# Breakout3v2.net
KiCad netlist of a schematic drawn in EAGLE
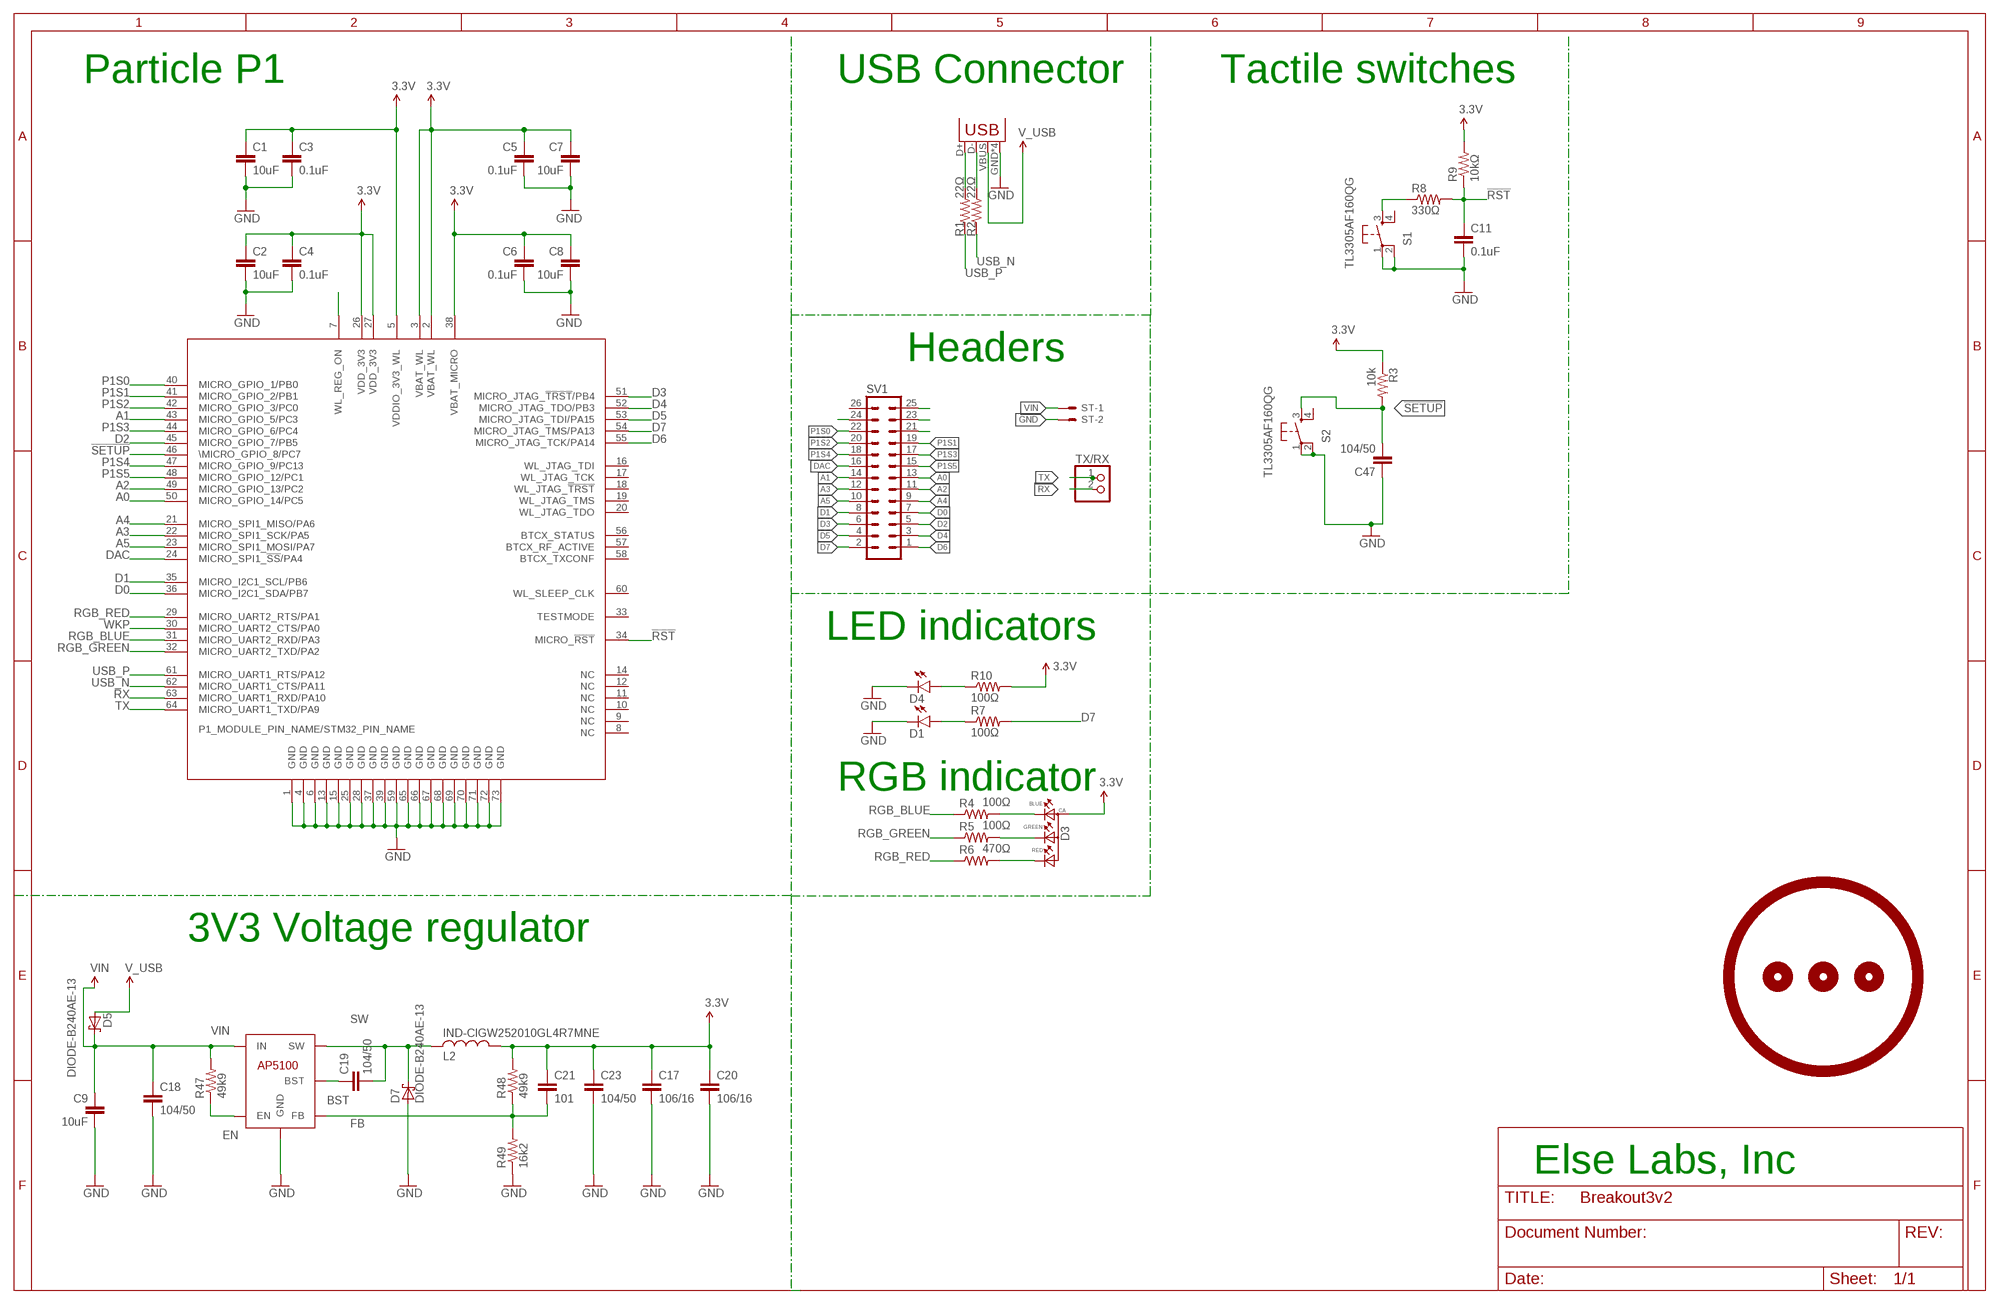
[diagram p0: schematic, sheet 1]

(export (version "E")
  (design (tool "Eeschema 10.0.6"))
  (components
    (comp (ref "C1")
      (value "10uF")
      (footprint "eagle-import:0805")
      (libsource (lib "eagle-import") (part "CAP0805"))
    )
    (comp (ref "C2")
      (value "10uF")
      (footprint "eagle-import:0805")
      (libsource (lib "eagle-import") (part "CAP0805"))
    )
    (comp (ref "C3")
      (value "0.1uF")
      (footprint "eagle-import:0805")
      (libsource (lib "eagle-import") (part "CAP0805"))
    )
    (comp (ref "C4")
      (value "0.1uF")
      (footprint "eagle-import:0805")
      (libsource (lib "eagle-import") (part "CAP0805"))
    )
    (comp (ref "C5")
      (value "0.1uF")
      (footprint "eagle-import:0805")
      (libsource (lib "eagle-import") (part "CAP0805"))
    )
    (comp (ref "C6")
      (value "0.1uF")
      (footprint "eagle-import:0805")
      (libsource (lib "eagle-import") (part "CAP0805"))
    )
    (comp (ref "C7")
      (value "10uF")
      (footprint "eagle-import:0805")
      (libsource (lib "eagle-import") (part "CAP0805"))
    )
    (comp (ref "C8")
      (value "10uF")
      (footprint "eagle-import:0805")
      (libsource (lib "eagle-import") (part "CAP0805"))
    )
    (comp (ref "C9")
      (value "10uF")
      (footprint "eagle-import:0805")
      (libsource (lib "eagle-import") (part "CAP0805"))
    )
    (comp (ref "C11")
      (value "0.1uF")
      (footprint "eagle-import:0805")
      (libsource (lib "eagle-import") (part "CAP0805"))
    )
    (comp (ref "C17")
      (value "106/16")
      (footprint "eagle-import:C0805")
      (libsource (lib "eagle-import") (part "C-EUC0805"))
    )
    (comp (ref "C18")
      (value "104/50")
      (footprint "eagle-import:C0603")
      (libsource (lib "eagle-import") (part "C-EUC0603"))
    )
    (comp (ref "C19")
      (value "104/50")
      (footprint "eagle-import:C0603")
      (libsource (lib "eagle-import") (part "C-EUC0603"))
    )
    (comp (ref "C20")
      (value "106/16")
      (footprint "eagle-import:C0805")
      (libsource (lib "eagle-import") (part "C-EUC0805"))
    )
    (comp (ref "C21")
      (value "101")
      (footprint "eagle-import:C0603")
      (libsource (lib "eagle-import") (part "C-EUC0603"))
    )
    (comp (ref "C23")
      (value "104/50")
      (footprint "eagle-import:C0603")
      (libsource (lib "eagle-import") (part "C-EUC0603"))
    )
    (comp (ref "C47")
      (value "104/50")
      (footprint "eagle-import:C0603")
      (libsource (lib "eagle-import") (part "C-EUC0603"))
    )
    (comp (ref "D1")
      (value "LED0603")
      (footprint "eagle-import:LED-0603")
      (libsource (lib "eagle-import") (part "LED0603"))
    )
    (comp (ref "D3")
      (value "CLVBA-FKAPLCC")
      (footprint "eagle-import:4-PLCC")
      (libsource (lib "eagle-import") (part "CLVBA-FKAPLCC"))
    )
    (comp (ref "D4")
      (value "LED0603")
      (footprint "eagle-import:LED-0603")
      (libsource (lib "eagle-import") (part "LED0603"))
    )
    (comp (ref "D5")
      (value "DIODE-B240AE-13")
      (footprint "eagle-import:DO-214AC")
      (libsource (lib "eagle-import") (part "DIODE-B240AE-13"))
    )
    (comp (ref "D7")
      (value "DIODE-B240AE-13")
      (footprint "eagle-import:DO-214AC")
      (libsource (lib "eagle-import") (part "DIODE-B240AE-13"))
    )
    (comp (ref "IC5")
      (value "SMSP-BUCK-AP5100")
      (footprint "eagle-import:SOT23-6")
      (libsource (lib "eagle-import") (part "SMSP-BUCK-AP5100"))
    )
    (comp (ref "JP1")
      (value "USBUSB-MICROB-SLOT-HOLE")
      (footprint "eagle-import:USB-MICROB-SLOT-HOLE")
      (libsource (lib "eagle-import") (part "USBUSB-MICROB-SLOT-HOLE"))
    )
    (comp (ref "L2")
      (value "IND-CIGW252010GL4R7MNE")
      (footprint "eagle-import:L2520")
      (libsource (lib "eagle-import") (part "IND-CIGW252010GL4R7MNE"))
    )
    (comp (ref "R1")
      (value "22Ω")
      (footprint "eagle-import:0805")
      (libsource (lib "eagle-import") (part "RESISTOR0805-RES"))
    )
    (comp (ref "R2")
      (value "22Ω")
      (footprint "eagle-import:0805")
      (libsource (lib "eagle-import") (part "RESISTOR0805-RES"))
    )
    (comp (ref "R3")
      (value "10k")
      (footprint "eagle-import:R0603")
      (libsource (lib "eagle-import") (part "R-US_R0603"))
    )
    (comp (ref "R4")
      (value "100Ω")
      (footprint "eagle-import:0805")
      (libsource (lib "eagle-import") (part "RESISTOR0805-RES"))
    )
    (comp (ref "R5")
      (value "100Ω")
      (footprint "eagle-import:0805")
      (libsource (lib "eagle-import") (part "RESISTOR0805-RES"))
    )
    (comp (ref "R6")
      (value "470Ω")
      (footprint "eagle-import:0805")
      (libsource (lib "eagle-import") (part "RESISTOR0805-RES"))
    )
    (comp (ref "R7")
      (value "100Ω")
      (footprint "eagle-import:0805")
      (libsource (lib "eagle-import") (part "RESISTOR0805-RES"))
    )
    (comp (ref "R8")
      (value "330Ω")
      (footprint "eagle-import:0805")
      (libsource (lib "eagle-import") (part "RESISTOR0805-RES"))
    )
    (comp (ref "R9")
      (value "10kΩ")
      (footprint "eagle-import:0805")
      (libsource (lib "eagle-import") (part "RESISTOR0805-RES"))
    )
    (comp (ref "R10")
      (value "100Ω")
      (footprint "eagle-import:0805")
      (libsource (lib "eagle-import") (part "RESISTOR0805-RES"))
    )
    (comp (ref "R47")
      (value "49k9")
      (footprint "eagle-import:R0603")
      (libsource (lib "eagle-import") (part "R-US_R0603"))
    )
    (comp (ref "R48")
      (value "49k9")
      (footprint "eagle-import:R0603")
      (libsource (lib "eagle-import") (part "R-US_R0603"))
    )
    (comp (ref "R49")
      (value "16k2")
      (footprint "eagle-import:R0603")
      (libsource (lib "eagle-import") (part "R-US_R0603"))
    )
    (comp (ref "S1")
      (value "TL3305AF160QG")
      (footprint "eagle-import:TACTILE_SWITCH_SMD_4.5X4.5MM")
      (libsource (lib "eagle-import") (part "SWITCH-MOMENTARY-4.5MX4.5M"))
    )
    (comp (ref "S2")
      (value "TL3305AF160QG")
      (footprint "eagle-import:TACTILE_SWITCH_SMD_4.5X4.5MM")
      (libsource (lib "eagle-import") (part "SWITCH-MOMENTARY-4.5MX4.5M"))
    )
    (comp (ref "ST")
      (value "22-27-2021-02")
      (footprint "eagle-import:6410-02")
      (fields (field (name "MF") "MOLEX"))
      (libsource (lib "eagle-import") (part "22-?-0227-2021"))
    )
    (comp (ref "SV1")
      (value "MA13-2")
      (footprint "eagle-import:MA13-2")
      (libsource (lib "eagle-import") (part "MA13-2"))
    )
    (comp (ref "TX/RX")
      (value "PINHD-1X2")
      (footprint "eagle-import:1X02")
      (libsource (lib "eagle-import") (part "PINHD-1X2"))
    )
    (comp (ref "U$1")
      (value "LOGO")
      (footprint "eagle-import:LOGO")
      (libsource (lib "eagle-import") (part "LOGO"))
    )
    (comp (ref "UC1")
      (value "P1")
      (footprint "eagle-import:WM-N-BM-14")
      (libsource (lib "eagle-import") (part "P1"))
    )
  )
  (nets
    (net (code "1") (name "/BST") (class "Default")
      (node (ref "C19") (pin "1") (pinfunction "1_1") (pintype "passive"))
      (node (ref "IC5") (pin "1") (pinfunction "BST_1") (pintype "bidirectional"))
    )
    (net (code "2") (name "/EN") (class "Default")
      (node (ref "IC5") (pin "4") (pinfunction "EN_4") (pintype "bidirectional"))
      (node (ref "R47") (pin "1") (pinfunction "1_1") (pintype "passive"))
    )
    (net (code "3") (name "/FB") (class "Default")
      (node (ref "C21") (pin "2") (pinfunction "2_2") (pintype "passive"))
      (node (ref "IC5") (pin "3") (pinfunction "FB_3") (pintype "bidirectional"))
      (node (ref "R48") (pin "1") (pinfunction "1_1") (pintype "passive"))
      (node (ref "R49") (pin "2") (pinfunction "2_2") (pintype "passive"))
    )
    (net (code "4") (name "/RGB_BLUE") (class "Default")
      (node (ref "R4") (pin "1") (pinfunction "1_1") (pintype "passive"))
      (node (ref "UC1") (pin "31") (pinfunction "MICRO_UART2_RXD/PA3_31") (pintype "bidirectional"))
    )
    (net (code "5") (name "/RGB_GREEN") (class "Default")
      (node (ref "R5") (pin "1") (pinfunction "1_1") (pintype "passive"))
      (node (ref "UC1") (pin "32") (pinfunction "MICRO_UART2_TXD/PA2_32") (pintype "bidirectional"))
    )
    (net (code "6") (name "/RGB_RED") (class "Default")
      (node (ref "R6") (pin "1") (pinfunction "1_1") (pintype "passive"))
      (node (ref "UC1") (pin "29") (pinfunction "MICRO_UART2_RTS/PA1_29") (pintype "bidirectional"))
    )
    (net (code "7") (name "/SW") (class "Default")
      (node (ref "C19") (pin "2") (pinfunction "2_2") (pintype "passive"))
      (node (ref "D7") (pin "C") (pinfunction "C_C") (pintype "passive"))
      (node (ref "IC5") (pin "6") (pinfunction "SW_6") (pintype "bidirectional"))
      (node (ref "L2") (pin "P$2") (pinfunction "2_P$2") (pintype "passive"))
    )
    (net (code "8") (name "/USB_N") (class "Default")
      (node (ref "R2") (pin "1") (pinfunction "1_1") (pintype "passive"))
      (node (ref "UC1") (pin "62") (pinfunction "MICRO_UART1_CTS/PA11_62") (pintype "bidirectional"))
    )
    (net (code "9") (name "/USB_P") (class "Default")
      (node (ref "R1") (pin "1") (pinfunction "1_1") (pintype "passive"))
      (node (ref "UC1") (pin "61") (pinfunction "MICRO_UART1_RTS/PA12_61") (pintype "bidirectional"))
    )
    (net (code "10") (name "/WKP") (class "Default")
      (node (ref "UC1") (pin "30") (pinfunction "MICRO_UART2_CTS/PA0_30") (pintype "bidirectional"))
    )
    (net (code "11") (name "/~{RST}") (class "Default")
      (node (ref "C11") (pin "1") (pinfunction "1_1") (pintype "passive"))
      (node (ref "R8") (pin "2") (pinfunction "2_2") (pintype "passive"))
      (node (ref "R9") (pin "1") (pinfunction "1_1") (pintype "passive"))
      (node (ref "UC1") (pin "34") (pinfunction "MICRO_~{RST}_34") (pintype "bidirectional"))
    )
    (net (code "12") (name "/~{SETUP}") (class "Default")
      (node (ref "C47") (pin "2") (pinfunction "2_2") (pintype "passive"))
      (node (ref "R3") (pin "2") (pinfunction "2_2") (pintype "passive"))
      (node (ref "S2") (pin "3") (pinfunction "3_3") (pintype "passive"))
      (node (ref "UC1") (pin "46") (pinfunction "\\MICRO_GPIO_8/PC7_46") (pintype "bidirectional"))
    )
    (net (code "13") (name "3.3V") (class "Default")
      (node (ref "C1") (pin "1") (pinfunction "1_1") (pintype "passive"))
      (node (ref "C17") (pin "1") (pinfunction "1_1") (pintype "passive"))
      (node (ref "C2") (pin "1") (pinfunction "1_1") (pintype "passive"))
      (node (ref "C20") (pin "1") (pinfunction "1_1") (pintype "passive"))
      (node (ref "C21") (pin "1") (pinfunction "1_1") (pintype "passive"))
      (node (ref "C23") (pin "1") (pinfunction "1_1") (pintype "passive"))
      (node (ref "C3") (pin "1") (pinfunction "1_1") (pintype "passive"))
      (node (ref "C4") (pin "1") (pinfunction "1_1") (pintype "passive"))
      (node (ref "C5") (pin "1") (pinfunction "1_1") (pintype "passive"))
      (node (ref "C6") (pin "1") (pinfunction "1_1") (pintype "passive"))
      (node (ref "C7") (pin "1") (pinfunction "1_1") (pintype "passive"))
      (node (ref "C8") (pin "1") (pinfunction "1_1") (pintype "passive"))
      (node (ref "D3") (pin "2") (pinfunction "ANODE_2") (pintype "passive"))
      (node (ref "L2") (pin "P$1") (pinfunction "1_P$1") (pintype "passive"))
      (node (ref "R10") (pin "2") (pinfunction "2_2") (pintype "passive"))
      (node (ref "R3") (pin "1") (pinfunction "1_1") (pintype "passive"))
      (node (ref "R48") (pin "2") (pinfunction "2_2") (pintype "passive"))
      (node (ref "R9") (pin "2") (pinfunction "2_2") (pintype "passive"))
      (node (ref "UC1") (pin "2") (pinfunction "VBAT_WL_2") (pintype "bidirectional"))
      (node (ref "UC1") (pin "26") (pinfunction "VDD_3V3_26") (pintype "bidirectional"))
      (node (ref "UC1") (pin "27") (pinfunction "VDD_3V3_27") (pintype "bidirectional"))
      (node (ref "UC1") (pin "3") (pinfunction "VBAT_WL_3") (pintype "bidirectional"))
      (node (ref "UC1") (pin "38") (pinfunction "VBAT_MICRO_38") (pintype "bidirectional"))
      (node (ref "UC1") (pin "5") (pinfunction "VDDIO_3V3_WL_5") (pintype "bidirectional"))
    )
    (net (code "14") (name "A0") (class "Default")
      (node (ref "SV1") (pin "13") (pinfunction "13_13") (pintype "passive"))
      (node (ref "UC1") (pin "50") (pinfunction "MICRO_GPIO_14/PC5_50") (pintype "bidirectional"))
    )
    (net (code "15") (name "A1") (class "Default")
      (node (ref "SV1") (pin "14") (pinfunction "14_14") (pintype "passive"))
      (node (ref "UC1") (pin "43") (pinfunction "MICRO_GPIO_5/PC3_43") (pintype "bidirectional"))
    )
    (net (code "16") (name "A2") (class "Default")
      (node (ref "SV1") (pin "11") (pinfunction "11_11") (pintype "passive"))
      (node (ref "UC1") (pin "49") (pinfunction "MICRO_GPIO_13/PC2_49") (pintype "bidirectional"))
    )
    (net (code "17") (name "A3") (class "Default")
      (node (ref "SV1") (pin "12") (pinfunction "12_12") (pintype "passive"))
      (node (ref "UC1") (pin "22") (pinfunction "MICRO_SPI1_SCK/PA5_22") (pintype "bidirectional"))
    )
    (net (code "18") (name "A4") (class "Default")
      (node (ref "SV1") (pin "9") (pinfunction "9_9") (pintype "passive"))
      (node (ref "UC1") (pin "21") (pinfunction "MICRO_SPI1_MISO/PA6_21") (pintype "bidirectional"))
    )
    (net (code "19") (name "A5") (class "Default")
      (node (ref "SV1") (pin "10") (pinfunction "10_10") (pintype "passive"))
      (node (ref "UC1") (pin "23") (pinfunction "MICRO_SPI1_MOSI/PA7_23") (pintype "bidirectional"))
    )
    (net (code "20") (name "D0") (class "Default")
      (node (ref "SV1") (pin "7") (pinfunction "7_7") (pintype "passive"))
      (node (ref "UC1") (pin "36") (pinfunction "MICRO_I2C1_SDA/PB7_36") (pintype "bidirectional"))
    )
    (net (code "21") (name "D1") (class "Default")
      (node (ref "SV1") (pin "8") (pinfunction "8_8") (pintype "passive"))
      (node (ref "UC1") (pin "35") (pinfunction "MICRO_I2C1_SCL/PB6_35") (pintype "bidirectional"))
    )
    (net (code "22") (name "D2") (class "Default")
      (node (ref "SV1") (pin "5") (pinfunction "5_5") (pintype "passive"))
      (node (ref "UC1") (pin "45") (pinfunction "MICRO_GPIO_7/PB5_45") (pintype "bidirectional"))
    )
    (net (code "23") (name "D3") (class "Default")
      (node (ref "SV1") (pin "6") (pinfunction "6_6") (pintype "passive"))
      (node (ref "UC1") (pin "51") (pinfunction "MICRO_JTAG_~{TRST}/PB4_51") (pintype "bidirectional"))
    )
    (net (code "24") (name "D4") (class "Default")
      (node (ref "SV1") (pin "3") (pinfunction "3_3") (pintype "passive"))
      (node (ref "UC1") (pin "52") (pinfunction "MICRO_JTAG_TDO/PB3_52") (pintype "bidirectional"))
    )
    (net (code "25") (name "D5") (class "Default")
      (node (ref "SV1") (pin "4") (pinfunction "4_4") (pintype "passive"))
      (node (ref "UC1") (pin "53") (pinfunction "MICRO_JTAG_TDI/PA15_53") (pintype "bidirectional"))
    )
    (net (code "26") (name "D6") (class "Default")
      (node (ref "SV1") (pin "1") (pinfunction "1_1") (pintype "passive"))
      (node (ref "UC1") (pin "55") (pinfunction "MICRO_JTAG_TCK/PA14_55") (pintype "bidirectional"))
    )
    (net (code "27") (name "D7") (class "Default")
      (node (ref "R7") (pin "2") (pinfunction "2_2") (pintype "passive"))
      (node (ref "SV1") (pin "2") (pinfunction "2_2") (pintype "passive"))
      (node (ref "UC1") (pin "54") (pinfunction "MICRO_JTAG_TMS/PA13_54") (pintype "bidirectional"))
    )
    (net (code "28") (name "DAC") (class "Default")
      (node (ref "SV1") (pin "16") (pinfunction "16_16") (pintype "passive"))
      (node (ref "UC1") (pin "24") (pinfunction "MICRO_SPI1_~{SS}/PA4_24") (pintype "bidirectional"))
    )
    (net (code "29") (name "GND") (class "Default")
      (node (ref "C1") (pin "2") (pinfunction "2_2") (pintype "passive"))
      (node (ref "C11") (pin "2") (pinfunction "2_2") (pintype "passive"))
      (node (ref "C17") (pin "2") (pinfunction "2_2") (pintype "passive"))
      (node (ref "C18") (pin "2") (pinfunction "2_2") (pintype "passive"))
      (node (ref "C2") (pin "2") (pinfunction "2_2") (pintype "passive"))
      (node (ref "C20") (pin "2") (pinfunction "2_2") (pintype "passive"))
      (node (ref "C23") (pin "2") (pinfunction "2_2") (pintype "passive"))
      (node (ref "C3") (pin "2") (pinfunction "2_2") (pintype "passive"))
      (node (ref "C4") (pin "2") (pinfunction "2_2") (pintype "passive"))
      (node (ref "C47") (pin "1") (pinfunction "1_1") (pintype "passive"))
      (node (ref "C5") (pin "2") (pinfunction "2_2") (pintype "passive"))
      (node (ref "C6") (pin "2") (pinfunction "2_2") (pintype "passive"))
      (node (ref "C7") (pin "2") (pinfunction "2_2") (pintype "passive"))
      (node (ref "C8") (pin "2") (pinfunction "2_2") (pintype "passive"))
      (node (ref "C9") (pin "2") (pinfunction "2_2") (pintype "passive"))
      (node (ref "D1") (pin "C") (pinfunction "C_C") (pintype "passive"))
      (node (ref "D4") (pin "C") (pinfunction "C_C") (pintype "passive"))
      (node (ref "D7") (pin "A") (pinfunction "A_A") (pintype "passive"))
      (node (ref "IC5") (pin "2") (pinfunction "GND_2") (pintype "bidirectional"))
      (node (ref "JP1") (pin "GND") (pinfunction "GND_GND") (pintype "bidirectional"))
      (node (ref "JP1") (pin "P$1") (pinfunction "GND_P$1") (pintype "bidirectional"))
      (node (ref "JP1") (pin "P$2") (pinfunction "GND_P$2") (pintype "bidirectional"))
      (node (ref "JP1") (pin "P$3") (pinfunction "GND_P$3") (pintype "bidirectional"))
      (node (ref "R49") (pin "1") (pinfunction "1_1") (pintype "passive"))
      (node (ref "S1") (pin "1") (pinfunction "1_1") (pintype "passive"))
      (node (ref "S1") (pin "2") (pinfunction "2_2") (pintype "passive"))
      (node (ref "S2") (pin "1") (pinfunction "1_1") (pintype "passive"))
      (node (ref "S2") (pin "2") (pinfunction "2_2") (pintype "passive"))
      (node (ref "ST") (pin "2") (pinfunction "S_2") (pintype "passive"))
      (node (ref "UC1") (pin "1") (pinfunction "GND_1") (pintype "bidirectional"))
      (node (ref "UC1") (pin "13") (pinfunction "GND_13") (pintype "bidirectional"))
      (node (ref "UC1") (pin "15") (pinfunction "GND_15") (pintype "bidirectional"))
      (node (ref "UC1") (pin "25") (pinfunction "GND_25") (pintype "bidirectional"))
      (node (ref "UC1") (pin "28") (pinfunction "GND_28") (pintype "bidirectional"))
      (node (ref "UC1") (pin "37") (pinfunction "GND_37") (pintype "bidirectional"))
      (node (ref "UC1") (pin "39") (pinfunction "GND_39") (pintype "bidirectional"))
      (node (ref "UC1") (pin "4") (pinfunction "GND_4") (pintype "bidirectional"))
      (node (ref "UC1") (pin "59") (pinfunction "GND_59") (pintype "bidirectional"))
      (node (ref "UC1") (pin "6") (pinfunction "GND_6") (pintype "bidirectional"))
      (node (ref "UC1") (pin "65") (pinfunction "GND_65") (pintype "bidirectional"))
      (node (ref "UC1") (pin "66") (pinfunction "GND_66") (pintype "bidirectional"))
      (node (ref "UC1") (pin "67") (pinfunction "GND_67") (pintype "bidirectional"))
      (node (ref "UC1") (pin "68") (pinfunction "GND_68") (pintype "bidirectional"))
      (node (ref "UC1") (pin "69") (pinfunction "GND_69") (pintype "bidirectional"))
      (node (ref "UC1") (pin "70") (pinfunction "GND_70") (pintype "bidirectional"))
      (node (ref "UC1") (pin "71") (pinfunction "GND_71") (pintype "bidirectional"))
      (node (ref "UC1") (pin "72") (pinfunction "GND_72") (pintype "bidirectional"))
      (node (ref "UC1") (pin "73") (pinfunction "GND_73") (pintype "bidirectional"))
    )
    (net (code "30") (name "Net-(D1-PadA)") (class "Default")
      (node (ref "D1") (pin "A") (pinfunction "A_A") (pintype "passive"))
      (node (ref "R7") (pin "1") (pinfunction "1_1") (pintype "passive"))
    )
    (net (code "31") (name "Net-(D3-BLUE)") (class "Default")
      (node (ref "D3") (pin "3") (pinfunction "BLUE_3") (pintype "passive"))
      (node (ref "R4") (pin "2") (pinfunction "2_2") (pintype "passive"))
    )
    (net (code "32") (name "Net-(D3-GREEN)") (class "Default")
      (node (ref "D3") (pin "4") (pinfunction "GREEN_4") (pintype "passive"))
      (node (ref "R5") (pin "2") (pinfunction "2_2") (pintype "passive"))
    )
    (net (code "33") (name "Net-(D3-RED)") (class "Default")
      (node (ref "D3") (pin "1") (pinfunction "RED_1") (pintype "passive"))
      (node (ref "R6") (pin "2") (pinfunction "2_2") (pintype "passive"))
    )
    (net (code "34") (name "Net-(D4-PadA)") (class "Default")
      (node (ref "D4") (pin "A") (pinfunction "A_A") (pintype "passive"))
      (node (ref "R10") (pin "1") (pinfunction "1_1") (pintype "passive"))
    )
    (net (code "35") (name "Net-(JP1-PadD+)") (class "Default")
      (node (ref "JP1") (pin "D+") (pinfunction "D+_D+") (pintype "bidirectional"))
      (node (ref "R1") (pin "2") (pinfunction "2_2") (pintype "passive"))
    )
    (net (code "36") (name "Net-(JP1-PadD-)") (class "Default")
      (node (ref "JP1") (pin "D-") (pinfunction "D-_D-") (pintype "bidirectional"))
      (node (ref "R2") (pin "2") (pinfunction "2_2") (pintype "passive"))
    )
    (net (code "37") (name "Net-(R8-Pad1)") (class "Default")
      (node (ref "R8") (pin "1") (pinfunction "1_1") (pintype "passive"))
      (node (ref "S1") (pin "3") (pinfunction "3_3") (pintype "passive"))
    )
    (net (code "38") (name "P1S0") (class "Default")
      (node (ref "SV1") (pin "22") (pinfunction "22_22") (pintype "passive"))
      (node (ref "UC1") (pin "40") (pinfunction "MICRO_GPIO_1/PB0_40") (pintype "bidirectional"))
    )
    (net (code "39") (name "P1S1") (class "Default")
      (node (ref "SV1") (pin "19") (pinfunction "19_19") (pintype "passive"))
      (node (ref "UC1") (pin "41") (pinfunction "MICRO_GPIO_2/PB1_41") (pintype "bidirectional"))
    )
    (net (code "40") (name "P1S2") (class "Default")
      (node (ref "SV1") (pin "20") (pinfunction "20_20") (pintype "passive"))
      (node (ref "UC1") (pin "42") (pinfunction "MICRO_GPIO_3/PC0_42") (pintype "bidirectional"))
    )
    (net (code "41") (name "P1S3") (class "Default")
      (node (ref "SV1") (pin "17") (pinfunction "17_17") (pintype "passive"))
      (node (ref "UC1") (pin "44") (pinfunction "MICRO_GPIO_6/PC4_44") (pintype "bidirectional"))
    )
    (net (code "42") (name "P1S4") (class "Default")
      (node (ref "SV1") (pin "18") (pinfunction "18_18") (pintype "passive"))
      (node (ref "UC1") (pin "47") (pinfunction "MICRO_GPIO_9/PC13_47") (pintype "bidirectional"))
    )
    (net (code "43") (name "P1S5") (class "Default")
      (node (ref "SV1") (pin "15") (pinfunction "15_15") (pintype "passive"))
      (node (ref "UC1") (pin "48") (pinfunction "MICRO_GPIO_12/PC1_48") (pintype "bidirectional"))
    )
    (net (code "44") (name "RX") (class "Default")
      (node (ref "TX/RX") (pin "2") (pinfunction "2_2") (pintype "passive"))
      (node (ref "UC1") (pin "63") (pinfunction "MICRO_UART1_RXD/PA10_63") (pintype "bidirectional"))
    )
    (net (code "45") (name "TX") (class "Default")
      (node (ref "TX/RX") (pin "1") (pinfunction "1_1") (pintype "passive"))
      (node (ref "UC1") (pin "64") (pinfunction "MICRO_UART1_TXD/PA9_64") (pintype "bidirectional"))
    )
    (net (code "46") (name "VIN") (class "Default")
      (node (ref "C18") (pin "1") (pinfunction "1_1") (pintype "passive"))
      (node (ref "C9") (pin "1") (pinfunction "1_1") (pintype "passive"))
      (node (ref "D5") (pin "C") (pinfunction "C_C") (pintype "passive"))
      (node (ref "IC5") (pin "5") (pinfunction "IN_5") (pintype "bidirectional"))
      (node (ref "R47") (pin "2") (pinfunction "2_2") (pintype "passive"))
      (node (ref "ST") (pin "1") (pinfunction "S_1") (pintype "passive"))
    )
    (net (code "47") (name "V_USB") (class "Default")
      (node (ref "D5") (pin "A") (pinfunction "A_A") (pintype "passive"))
      (node (ref "JP1") (pin "VBUS") (pinfunction "VBUS_VBUS") (pintype "bidirectional"))
    )
    (net (code "48") (name "unconnected-(S1-Pad4)") (class "Default")
      (node (ref "S1") (pin "4") (pinfunction "4_4") (pintype "passive"))
    )
    (net (code "49") (name "unconnected-(S2-Pad4)") (class "Default")
      (node (ref "S2") (pin "4") (pinfunction "4_4") (pintype "passive"))
    )
    (net (code "50") (name "unconnected-(SV1-Pad21)") (class "Default")
      (node (ref "SV1") (pin "21") (pinfunction "21_21") (pintype "passive"))
    )
    (net (code "51") (name "unconnected-(SV1-Pad23)") (class "Default")
      (node (ref "SV1") (pin "23") (pinfunction "23_23") (pintype "passive"))
    )
    (net (code "52") (name "unconnected-(SV1-Pad24)") (class "Default")
      (node (ref "SV1") (pin "24") (pinfunction "24_24") (pintype "passive"))
    )
    (net (code "53") (name "unconnected-(SV1-Pad25)") (class "Default")
      (node (ref "SV1") (pin "25") (pinfunction "25_25") (pintype "passive"))
    )
    (net (code "54") (name "unconnected-(SV1-Pad26)") (class "Default")
      (node (ref "SV1") (pin "26") (pinfunction "26_26") (pintype "passive"))
    )
    (net (code "55") (name "unconnected-(UC1-BTCX_RF_ACTIVE-Pad57)") (class "Default")
      (node (ref "UC1") (pin "57") (pinfunction "BTCX_RF_ACTIVE_57") (pintype "bidirectional"))
    )
    (net (code "56") (name "unconnected-(UC1-BTCX_STATUS-Pad56)") (class "Default")
      (node (ref "UC1") (pin "56") (pinfunction "BTCX_STATUS_56") (pintype "bidirectional"))
    )
    (net (code "57") (name "unconnected-(UC1-BTCX_TXCONF-Pad58)") (class "Default")
      (node (ref "UC1") (pin "58") (pinfunction "BTCX_TXCONF_58") (pintype "bidirectional"))
    )
    (net (code "58") (name "unconnected-(UC1-NC-Pad8)") (class "Default")
      (node (ref "UC1") (pin "8") (pinfunction "NC_8") (pintype "bidirectional"))
    )
    (net (code "59") (name "unconnected-(UC1-NC-Pad9)") (class "Default")
      (node (ref "UC1") (pin "9") (pinfunction "NC_9") (pintype "bidirectional"))
    )
    (net (code "60") (name "unconnected-(UC1-NC-Pad10)") (class "Default")
      (node (ref "UC1") (pin "10") (pinfunction "NC_10") (pintype "bidirectional"))
    )
    (net (code "61") (name "unconnected-(UC1-NC-Pad11)") (class "Default")
      (node (ref "UC1") (pin "11") (pinfunction "NC_11") (pintype "bidirectional"))
    )
    (net (code "62") (name "unconnected-(UC1-NC-Pad12)") (class "Default")
      (node (ref "UC1") (pin "12") (pinfunction "NC_12") (pintype "bidirectional"))
    )
    (net (code "63") (name "unconnected-(UC1-NC-Pad14)") (class "Default")
      (node (ref "UC1") (pin "14") (pinfunction "NC_14") (pintype "bidirectional"))
    )
    (net (code "64") (name "unconnected-(UC1-TESTMODE-Pad33)") (class "Default")
      (node (ref "UC1") (pin "33") (pinfunction "TESTMODE_33") (pintype "bidirectional"))
    )
    (net (code "65") (name "unconnected-(UC1-WL_JTAG_TCK-Pad17)") (class "Default")
      (node (ref "UC1") (pin "17") (pinfunction "WL_JTAG_TCK_17") (pintype "bidirectional"))
    )
    (net (code "66") (name "unconnected-(UC1-WL_JTAG_TDI-Pad16)") (class "Default")
      (node (ref "UC1") (pin "16") (pinfunction "WL_JTAG_TDI_16") (pintype "bidirectional"))
    )
    (net (code "67") (name "unconnected-(UC1-WL_JTAG_TDO-Pad20)") (class "Default")
      (node (ref "UC1") (pin "20") (pinfunction "WL_JTAG_TDO_20") (pintype "bidirectional"))
    )
    (net (code "68") (name "unconnected-(UC1-WL_JTAG_TMS-Pad19)") (class "Default")
      (node (ref "UC1") (pin "19") (pinfunction "WL_JTAG_TMS_19") (pintype "bidirectional"))
    )
    (net (code "69") (name "unconnected-(UC1-WL_JTAG_~{TRST}-Pad18)") (class "Default")
      (node (ref "UC1") (pin "18") (pinfunction "WL_JTAG_~{TRST}_18") (pintype "bidirectional"))
    )
    (net (code "70") (name "unconnected-(UC1-WL_REG_ON-Pad7)") (class "Default")
      (node (ref "UC1") (pin "7") (pinfunction "WL_REG_ON_7") (pintype "bidirectional"))
    )
    (net (code "71") (name "unconnected-(UC1-WL_SLEEP_CLK-Pad60)") (class "Default")
      (node (ref "UC1") (pin "60") (pinfunction "WL_SLEEP_CLK_60") (pintype "bidirectional"))
    )
  )
)
